# CW340_SAM3X_MAIN.net
KiCad netlist of a schematic drawn in Altium Designer
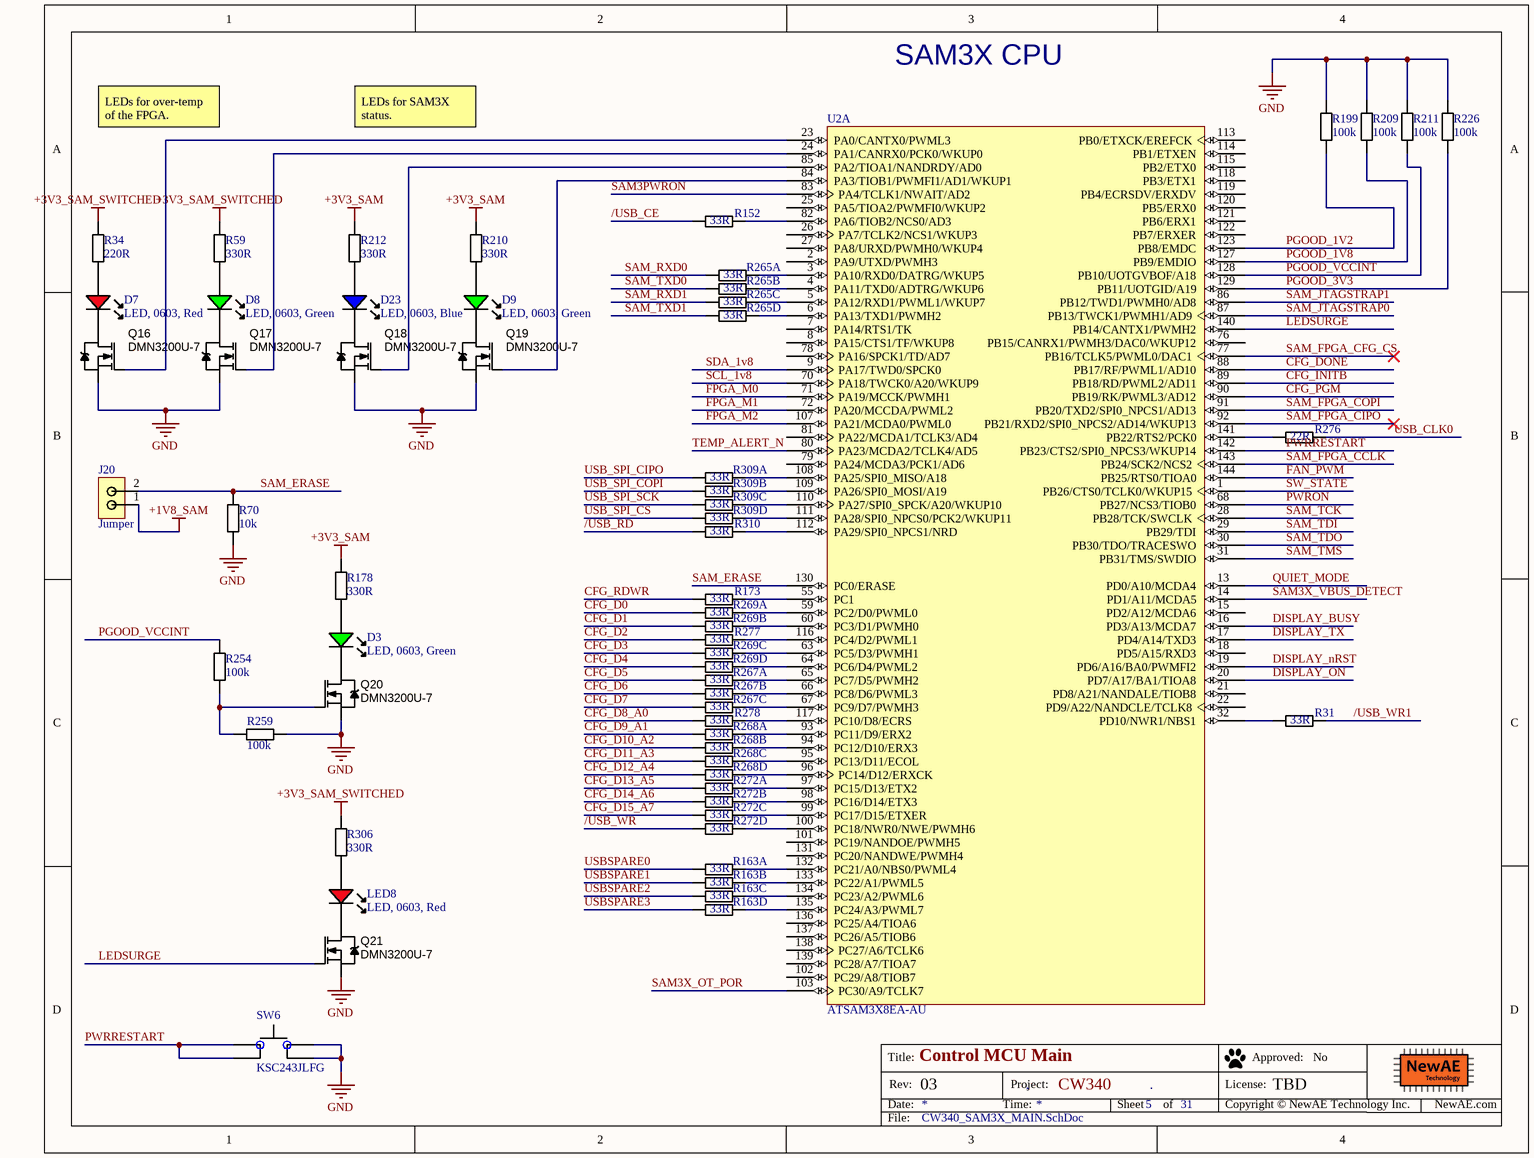
[diagram p0: CW340_SAM3X_MAIN.SchDoc]

(export (version "E")
  (design (tool "Eeschema 10.0.6"))
  (components
    (comp (ref "D3")
      (value "LED, 0603, Green")
      (footprint "LED-0603-GREEN")
      (description "Chip LED, Green")
      (fields (field (name "PART NUMBER") "LEDCHIP_0603_GREEN"))
      (libsource (lib "NewAE_AltiumLib") (part "LED_GREEN"))
    )
    (comp (ref "D7")
      (value "LED, 0603, Red")
      (footprint "LED-0603-RED")
      (description "Chip LED, Red")
      (fields (field (name "PART NUMBER") "LEDCHIP_0603_RED"))
      (libsource (lib "NewAE_AltiumLib") (part "LED_RED"))
    )
    (comp (ref "D8")
      (value "LED, 0603, Green")
      (footprint "LED-0603-GREEN")
      (description "Chip LED, Green")
      (fields (field (name "PART NUMBER") "LEDCHIP_0603_GREEN"))
      (libsource (lib "NewAE_AltiumLib") (part "LED_GREEN"))
    )
    (comp (ref "D9")
      (value "LED, 0603, Green")
      (footprint "LED-0603-GREEN")
      (description "Chip LED, Green")
      (fields (field (name "PART NUMBER") "LEDCHIP_0603_GREEN"))
      (libsource (lib "NewAE_AltiumLib") (part "LED_GREEN"))
    )
    (comp (ref "D23")
      (value "LED, 0603, Blue")
      (footprint "LED-0603-BLUE")
      (description "Chip LED, Blue")
      (fields (field (name "PART NUMBER") "LEDCHIP_0603_BLUE"))
      (libsource (lib "NewAE_AltiumLib") (part "LED_BLUE"))
    )
    (comp (ref "J20")
      (value "Jumper")
      (footprint "2x2.54mm_Header")
      (description "1x2 2.54mm header, male pins")
      (fields (field (name "PART NUMBER") "2_PIN_JUMPER"))
      (libsource (lib "NewAE_AltiumLib") (part "1x2_Pin_Header"))
    )
    (comp (ref "LED8")
      (value "LED, 0603, Red")
      (footprint "LED-0603-RED")
      (description "Chip LED, Red")
      (fields (field (name "PART NUMBER") "LEDCHIP_0603_RED"))
      (libsource (lib "NewAE_AltiumLib") (part "LED_RED"))
    )
    (comp (ref "Q16")
      (value "DMN3200U-7")
      (footprint "SOT95P245X110-3M")
      (description "MOSFET N-CH 30V 2.2A SOT23-3")
      (libsource (lib "NewAE_AltiumLib") (part "MOSFET_N_GSD"))
    )
    (comp (ref "Q17")
      (value "DMN3200U-7")
      (footprint "SOT95P245X110-3M")
      (description "MOSFET N-CH 30V 2.2A SOT23-3")
      (libsource (lib "NewAE_AltiumLib") (part "MOSFET_N_GSD"))
    )
    (comp (ref "Q18")
      (value "DMN3200U-7")
      (footprint "SOT95P245X110-3M")
      (description "MOSFET N-CH 30V 2.2A SOT23-3")
      (libsource (lib "NewAE_AltiumLib") (part "MOSFET_N_GSD"))
    )
    (comp (ref "Q19")
      (value "DMN3200U-7")
      (footprint "SOT95P245X110-3M")
      (description "MOSFET N-CH 30V 2.2A SOT23-3")
      (libsource (lib "NewAE_AltiumLib") (part "MOSFET_N_GSD"))
    )
    (comp (ref "Q20")
      (value "DMN3200U-7")
      (footprint "SOT95P245X110-3M")
      (description "MOSFET N-CH 30V 2.2A SOT23-3")
      (libsource (lib "NewAE_AltiumLib") (part "MOSFET_N_GSD"))
    )
    (comp (ref "Q21")
      (value "DMN3200U-7")
      (footprint "SOT95P245X110-3M")
      (description "MOSFET N-CH 30V 2.2A SOT23-3")
      (libsource (lib "NewAE_AltiumLib") (part "MOSFET_N_GSD"))
    )
    (comp (ref "R31")
      (value "33R")
      (footprint "RESC1005X40N")
      (description "33R res, 0402, 1%, 1/16W")
      (fields (field (name "PART NUMBER") "RCHIP-33R-0402") (field (name "TOLERANCE") "1%"))
      (libsource (lib "NewAE_AltiumLib") (part "RES-EU"))
    )
    (comp (ref "R34")
      (value "220R")
      (footprint "RESC1608X55N")
      (description "220R res, 0603, 1%, 1/10W")
      (fields (field (name "PART NUMBER") "RCHIP-220R-0603") (field (name "TOLERANCE") "1%"))
      (libsource (lib "") (part "RES-EU_1"))
    )
    (comp (ref "R59")
      (value "330R")
      (footprint "RESC1608X55N")
      (description "330R res, 0603, 1%, 1/10W")
      (fields (field (name "PART NUMBER") "RCHIP-330R-0603") (field (name "TOLERANCE") "1%"))
      (libsource (lib "") (part "RES-EU_1"))
    )
    (comp (ref "R70")
      (value "10k")
      (footprint "RESC1005X40N")
      (description "10k res, 0402, 1%, 1/16W")
      (fields (field (name "PART NUMBER") "RCHIP-10K-0402") (field (name "TOLERANCE") "1%"))
      (libsource (lib "") (part "RES-EU_2"))
    )
    (comp (ref "R152")
      (value "33R")
      (footprint "RESC1005X40N")
      (description "33R res, 0402, 1%, 1/16W")
      (fields (field (name "PART NUMBER") "RCHIP-33R-0402") (field (name "TOLERANCE") "1%"))
      (libsource (lib "NewAE_AltiumLib") (part "RES-EU"))
    )
    (comp (ref "R163")
      (value "33R")
      (footprint "741C083")
      (description "33-ohm, 0.5mm res array")
      (fields (field (name "PART NUMBER") "741C083330JP"))
      (libsource (lib "NewAE_AltiumLib") (part "RES-EU-4ARRAY"))
    )
    (comp (ref "R173")
      (value "33R")
      (footprint "RESC1005X40N")
      (description "33R res, 0402, 1%, 1/16W")
      (fields (field (name "PART NUMBER") "RCHIP-33R-0402") (field (name "TOLERANCE") "1%"))
      (libsource (lib "NewAE_AltiumLib") (part "RES-EU"))
    )
    (comp (ref "R178")
      (value "330R")
      (footprint "RESC1608X55N")
      (description "330R res, 0603, 1%, 1/10W")
      (fields (field (name "PART NUMBER") "RCHIP-330R-0603") (field (name "TOLERANCE") "1%"))
      (libsource (lib "") (part "RES-EU_1"))
    )
    (comp (ref "R199")
      (value "100k")
      (footprint "RESC1608X55N")
      (description "100k res, 0603, 1%, 1/10W")
      (fields (field (name "PART NUMBER") "RCHIP-100K-0603") (field (name "TOLERANCE") "1%"))
      (libsource (lib "") (part "RES-EU_2"))
    )
    (comp (ref "R209")
      (value "100k")
      (footprint "RESC1608X55N")
      (description "100k res, 0603, 1%, 1/10W")
      (fields (field (name "PART NUMBER") "RCHIP-100K-0603") (field (name "TOLERANCE") "1%"))
      (libsource (lib "") (part "RES-EU_2"))
    )
    (comp (ref "R210")
      (value "330R")
      (footprint "RESC1608X55N")
      (description "330R res, 0603, 1%, 1/10W")
      (fields (field (name "PART NUMBER") "RCHIP-330R-0603") (field (name "TOLERANCE") "1%"))
      (libsource (lib "") (part "RES-EU_1"))
    )
    (comp (ref "R211")
      (value "100k")
      (footprint "RESC1608X55N")
      (description "100k res, 0603, 1%, 1/10W")
      (fields (field (name "PART NUMBER") "RCHIP-100K-0603") (field (name "TOLERANCE") "1%"))
      (libsource (lib "") (part "RES-EU_2"))
    )
    (comp (ref "R212")
      (value "330R")
      (footprint "RESC1608X55N")
      (description "330R res, 0603, 1%, 1/10W")
      (fields (field (name "PART NUMBER") "RCHIP-330R-0603") (field (name "TOLERANCE") "1%"))
      (libsource (lib "") (part "RES-EU_1"))
    )
    (comp (ref "R226")
      (value "100k")
      (footprint "RESC1608X55N")
      (description "100k res, 0603, 1%, 1/10W")
      (fields (field (name "PART NUMBER") "RCHIP-100K-0603") (field (name "TOLERANCE") "1%"))
      (libsource (lib "") (part "RES-EU_2"))
    )
    (comp (ref "R254")
      (value "100k")
      (footprint "RESC1608X55N")
      (description "100k res, 0603, 1%, 1/10W")
      (fields (field (name "PART NUMBER") "RCHIP-100K-0603") (field (name "TOLERANCE") "1%"))
      (libsource (lib "") (part "RES-EU_2"))
    )
    (comp (ref "R259")
      (value "100k")
      (footprint "RESC1608X55N")
      (description "100k res, 0603, 1%, 1/10W")
      (fields (field (name "PART NUMBER") "RCHIP-100K-0603") (field (name "TOLERANCE") "1%"))
      (libsource (lib "NewAE_AltiumLib") (part "RES-EU"))
    )
    (comp (ref "R265")
      (value "33R")
      (footprint "741C083")
      (description "33-ohm, 0.5mm res array")
      (fields (field (name "PART NUMBER") "741C083330JP"))
      (libsource (lib "NewAE_AltiumLib") (part "RES-EU-4ARRAY"))
    )
    (comp (ref "R267")
      (value "33R")
      (footprint "741C083")
      (description "33-ohm, 0.5mm res array")
      (fields (field (name "PART NUMBER") "741C083330JP"))
      (libsource (lib "NewAE_AltiumLib") (part "RES-EU-4ARRAY"))
    )
    (comp (ref "R268")
      (value "33R")
      (footprint "741C083")
      (description "33-ohm, 0.5mm res array")
      (fields (field (name "PART NUMBER") "741C083330JP"))
      (libsource (lib "NewAE_AltiumLib") (part "RES-EU-4ARRAY"))
    )
    (comp (ref "R269")
      (value "33R")
      (footprint "741C083")
      (description "33-ohm, 0.5mm res array")
      (fields (field (name "PART NUMBER") "741C083330JP"))
      (libsource (lib "NewAE_AltiumLib") (part "RES-EU-4ARRAY"))
    )
    (comp (ref "R272")
      (value "33R")
      (footprint "741C083")
      (description "33-ohm, 0.5mm res array")
      (fields (field (name "PART NUMBER") "741C083330JP"))
      (libsource (lib "NewAE_AltiumLib") (part "RES-EU-4ARRAY"))
    )
    (comp (ref "R276")
      (value "22R")
      (footprint "RESC1005X40N")
      (description "22R res, 0402, 1%, 1/16W")
      (fields (field (name "PART NUMBER") "RCHIP-22R-0402") (field (name "TOLERANCE") "1%"))
      (libsource (lib "NewAE_AltiumLib") (part "RES-EU"))
    )
    (comp (ref "R277")
      (value "33R")
      (footprint "RESC1005X40N")
      (description "33R res, 0402, 1%, 1/16W")
      (fields (field (name "PART NUMBER") "RCHIP-33R-0402") (field (name "TOLERANCE") "1%"))
      (libsource (lib "NewAE_AltiumLib") (part "RES-EU"))
    )
    (comp (ref "R278")
      (value "33R")
      (footprint "RESC1005X40N")
      (description "33R res, 0402, 1%, 1/16W")
      (fields (field (name "PART NUMBER") "RCHIP-33R-0402") (field (name "TOLERANCE") "1%"))
      (libsource (lib "NewAE_AltiumLib") (part "RES-EU"))
    )
    (comp (ref "R306")
      (value "330R")
      (footprint "RESC1608X55N")
      (description "330R res, 0603, 1%, 1/10W")
      (fields (field (name "PART NUMBER") "RCHIP-330R-0603") (field (name "TOLERANCE") "1%"))
      (libsource (lib "") (part "RES-EU_1"))
    )
    (comp (ref "R309")
      (value "33R")
      (footprint "741C083")
      (description "33-ohm, 0.5mm res array")
      (fields (field (name "PART NUMBER") "741C083330JP"))
      (libsource (lib "NewAE_AltiumLib") (part "RES-EU-4ARRAY"))
    )
    (comp (ref "R310")
      (value "33R")
      (footprint "RESC1005X40N")
      (description "33R res, 0402, 1%, 1/16W")
      (fields (field (name "PART NUMBER") "RCHIP-33R-0402") (field (name "TOLERANCE") "1%"))
      (libsource (lib "NewAE_AltiumLib") (part "RES-EU"))
    )
    (comp (ref "SW6")
      (value "KSC243JLFG")
      (footprint "CK_KSC2J")
      (description "SWITCH TACTILE SPST-NO 0.01A 32V")
      (fields (field (name "PART NUMBER") "TACTSW-KSC243J"))
      (libsource (lib "NewAE_AltiumLib") (part "SW_PB_NO_4PIN_TACT"))
    )
    (comp (ref "U2")
      (value "ATSAM3X8EA-AU")
      (footprint "LQFP144_L")
      (fields (field (name "MANUFACTURER") "Atmel"))
      (libsource (lib "Altium Content Vault") (part "ATML-ATSAM3X-LQFP-144"))
    )
  )
  (nets
    (net (code "1") (name "+1V8_SAM") (class "Default")
      (node (ref "J20") (pin "1") (pinfunction "1_1") (pintype "passive"))
    )
    (net (code "2") (name "+3V3_SAM") (class "Default")
      (node (ref "R178") (pin "2") (pinfunction "2_2") (pintype "passive"))
      (node (ref "R210") (pin "2") (pinfunction "2_2") (pintype "passive"))
      (node (ref "R212") (pin "2") (pinfunction "2_2") (pintype "passive"))
    )
    (net (code "3") (name "+3V3_SAM_SWITCHED") (class "Default")
      (node (ref "R306") (pin "2") (pinfunction "2_2") (pintype "passive"))
      (node (ref "R34") (pin "2") (pinfunction "2_2") (pintype "passive"))
      (node (ref "R59") (pin "2") (pinfunction "2_2") (pintype "passive"))
    )
    (net (code "4") (name "/CFG_D0") (class "Default")
      (node (ref "R269") (pin "1A") (pinfunction "1A_1A") (pintype "passive"))
    )
    (net (code "5") (name "/CFG_D1") (class "Default")
      (node (ref "R269") (pin "2A") (pinfunction "2A_2A") (pintype "passive"))
    )
    (net (code "6") (name "/CFG_D2") (class "Default")
      (node (ref "R277") (pin "1") (pinfunction "1_1") (pintype "passive"))
    )
    (net (code "7") (name "/CFG_D3") (class "Default")
      (node (ref "R269") (pin "3A") (pinfunction "3A_3A") (pintype "passive"))
    )
    (net (code "8") (name "/CFG_D4") (class "Default")
      (node (ref "R269") (pin "4A") (pinfunction "4A_4A") (pintype "passive"))
    )
    (net (code "9") (name "/CFG_D5") (class "Default")
      (node (ref "R267") (pin "1A") (pinfunction "1A_1A") (pintype "passive"))
    )
    (net (code "10") (name "/CFG_D6") (class "Default")
      (node (ref "R267") (pin "2A") (pinfunction "2A_2A") (pintype "passive"))
    )
    (net (code "11") (name "/CFG_D7") (class "Default")
      (node (ref "R267") (pin "3A") (pinfunction "3A_3A") (pintype "passive"))
    )
    (net (code "12") (name "/CFG_D8_A0") (class "Default")
      (node (ref "R278") (pin "1") (pinfunction "1_1") (pintype "passive"))
    )
    (net (code "13") (name "/CFG_D9_A1") (class "Default")
      (node (ref "R268") (pin "1A") (pinfunction "1A_1A") (pintype "passive"))
    )
    (net (code "14") (name "/CFG_D10_A2") (class "Default")
      (node (ref "R268") (pin "2A") (pinfunction "2A_2A") (pintype "passive"))
    )
    (net (code "15") (name "/CFG_D11_A3") (class "Default")
      (node (ref "R268") (pin "3A") (pinfunction "3A_3A") (pintype "passive"))
    )
    (net (code "16") (name "/CFG_D12_A4") (class "Default")
      (node (ref "R268") (pin "4A") (pinfunction "4A_4A") (pintype "passive"))
    )
    (net (code "17") (name "/CFG_D13_A5") (class "Default")
      (node (ref "R272") (pin "1A") (pinfunction "1A_1A") (pintype "passive"))
    )
    (net (code "18") (name "/CFG_D14_A6") (class "Default")
      (node (ref "R272") (pin "2A") (pinfunction "2A_2A") (pintype "passive"))
    )
    (net (code "19") (name "/CFG_D15_A7") (class "Default")
      (node (ref "R272") (pin "3A") (pinfunction "3A_3A") (pintype "passive"))
    )
    (net (code "20") (name "/CFG_DONE") (class "Default")
      (node (ref "U2") (pin "88") (pinfunction "PB17/RF/PWML1/AD10_88") (pintype "bidirectional"))
    )
    (net (code "21") (name "/CFG_INITB") (class "Default")
      (node (ref "U2") (pin "89") (pinfunction "PB18/RD/PWML2/AD11_89") (pintype "bidirectional"))
    )
    (net (code "22") (name "/CFG_PGM") (class "Default")
      (node (ref "U2") (pin "90") (pinfunction "PB19/RK/PWML3/AD12_90") (pintype "bidirectional"))
    )
    (net (code "23") (name "/CFG_RDWR") (class "Default")
      (node (ref "R173") (pin "1") (pinfunction "1_1") (pintype "passive"))
    )
    (net (code "24") (name "/DISPLAY_BUSY") (class "Default")
      (node (ref "U2") (pin "16") (pinfunction "PD3/A13/MCDA7_16") (pintype "bidirectional"))
    )
    (net (code "25") (name "/DISPLAY_ON") (class "Default")
      (node (ref "U2") (pin "20") (pinfunction "PD7/A17/BA1/TIOA8_20") (pintype "bidirectional"))
    )
    (net (code "26") (name "/DISPLAY_TX") (class "Default")
      (node (ref "U2") (pin "17") (pinfunction "PD4/A14/TXD3_17") (pintype "bidirectional"))
    )
    (net (code "27") (name "/DISPLAY_nRST") (class "Default")
      (node (ref "U2") (pin "19") (pinfunction "PD6/A16/BA0/PWMFI2_19") (pintype "bidirectional"))
    )
    (net (code "28") (name "/FAN_PWM") (class "Default")
      (node (ref "U2") (pin "144") (pinfunction "PB25/RTS0/TIOA0_144") (pintype "bidirectional"))
    )
    (net (code "29") (name "/FPGA_M0") (class "Default")
      (node (ref "U2") (pin "71") (pinfunction "PA19/MCCK/PWMH1_71") (pintype "bidirectional"))
    )
    (net (code "30") (name "/FPGA_M1") (class "Default")
      (node (ref "U2") (pin "72") (pinfunction "PA20/MCCDA/PWML2_72") (pintype "bidirectional"))
    )
    (net (code "31") (name "/FPGA_M2") (class "Default")
      (node (ref "U2") (pin "107") (pinfunction "PA21/MCDA0/PWML0_107") (pintype "bidirectional"))
    )
    (net (code "32") (name "/LEDSURGE") (class "Default")
      (node (ref "Q21") (pin "1") (pinfunction "G_1") (pintype "passive"))
      (node (ref "U2") (pin "140") (pinfunction "PB14/CANTX1/PWMH2_140") (pintype "bidirectional"))
    )
    (net (code "33") (name "/PGOOD_1V2") (class "Default")
      (node (ref "R199") (pin "2") (pinfunction "2_2") (pintype "passive"))
      (node (ref "U2") (pin "123") (pinfunction "PB8/EMDC_123") (pintype "bidirectional"))
    )
    (net (code "34") (name "/PGOOD_1V8") (class "Default")
      (node (ref "R209") (pin "2") (pinfunction "2_2") (pintype "passive"))
      (node (ref "U2") (pin "127") (pinfunction "PB9/EMDIO_127") (pintype "bidirectional"))
    )
    (net (code "35") (name "/PGOOD_3V3") (class "Default")
      (node (ref "R226") (pin "2") (pinfunction "2_2") (pintype "passive"))
      (node (ref "U2") (pin "129") (pinfunction "PB11/UOTGID/A19_129") (pintype "bidirectional"))
    )
    (net (code "36") (name "/PGOOD_VCCINT") (class "Default")
      (node (ref "R211") (pin "2") (pinfunction "2_2") (pintype "passive"))
      (node (ref "R254") (pin "1") (pinfunction "1_1") (pintype "passive"))
      (node (ref "U2") (pin "128") (pinfunction "PB10/UOTGVBOF/A18_128") (pintype "bidirectional"))
    )
    (net (code "37") (name "/PWRON") (class "Default")
      (node (ref "U2") (pin "68") (pinfunction "PB27/NCS3/TIOB0_68") (pintype "bidirectional"))
    )
    (net (code "38") (name "/PWRRESTART") (class "Default")
      (node (ref "SW6") (pin "1") (pinfunction "IN_1") (pintype "passive"))
      (node (ref "SW6") (pin "4") (pinfunction "IN_4") (pintype "passive"))
      (node (ref "U2") (pin "142") (pinfunction "PB23/CTS2/SPI0_NPCS3/WKUP14_142") (pintype "bidirectional"))
    )
    (net (code "39") (name "/QUIET_MODE") (class "Default")
      (node (ref "U2") (pin "13") (pinfunction "PD0/A10/MCDA4_13") (pintype "bidirectional"))
    )
    (net (code "40") (name "/SAM3PWRON") (class "Default")
      (node (ref "U2") (pin "83") (pinfunction "PA4/TCLK1/NWAIT/AD2_83") (pintype "bidirectional"))
    )
    (net (code "41") (name "/SAM3X_OT_POR") (class "Default")
      (node (ref "U2") (pin "103") (pinfunction "PC30/A9/TCLK7_103") (pintype "bidirectional"))
    )
    (net (code "42") (name "/SAM3X_VBUS_DETECT") (class "Default")
      (node (ref "U2") (pin "14") (pinfunction "PD1/A11/MCDA5_14") (pintype "bidirectional"))
    )
    (net (code "43") (name "/SAM_ERASE") (class "Default")
      (node (ref "J20") (pin "2") (pinfunction "2_2") (pintype "passive"))
      (node (ref "R70") (pin "1") (pinfunction "1_1") (pintype "passive"))
      (node (ref "U2") (pin "130") (pinfunction "PC0/ERASE_130") (pintype "bidirectional"))
    )
    (net (code "44") (name "/SAM_FPGA_CCLK") (class "Default")
      (node (ref "U2") (pin "143") (pinfunction "PB24/SCK2/NCS2_143") (pintype "bidirectional"))
    )
    (net (code "45") (name "/SAM_FPGA_CFG_CS") (class "Default")
      (node (ref "U2") (pin "77") (pinfunction "PB16/TCLK5/PWML0/DAC1_77") (pintype "bidirectional+no_connect"))
    )
    (net (code "46") (name "/SAM_FPGA_CIPO") (class "Default")
      (node (ref "U2") (pin "92") (pinfunction "PB21/RXD2/SPI0_NPCS2/AD14/WKUP13_92") (pintype "bidirectional+no_connect"))
    )
    (net (code "47") (name "/SAM_FPGA_COPI") (class "Default")
      (node (ref "U2") (pin "91") (pinfunction "PB20/TXD2/SPI0_NPCS1/AD13_91") (pintype "bidirectional"))
    )
    (net (code "48") (name "/SAM_JTAGSTRAP0") (class "Default")
      (node (ref "U2") (pin "87") (pinfunction "PB13/TWCK1/PWMH1/AD9_87") (pintype "bidirectional"))
    )
    (net (code "49") (name "/SAM_JTAGSTRAP1") (class "Default")
      (node (ref "U2") (pin "86") (pinfunction "PB12/TWD1/PWMH0/AD8_86") (pintype "bidirectional"))
    )
    (net (code "50") (name "/SAM_RXD0") (class "Default")
      (node (ref "R265") (pin "1A") (pinfunction "1A_1A") (pintype "passive"))
    )
    (net (code "51") (name "/SAM_RXD1") (class "Default")
      (node (ref "R265") (pin "3A") (pinfunction "3A_3A") (pintype "passive"))
    )
    (net (code "52") (name "/SAM_TCK") (class "Default")
      (node (ref "U2") (pin "28") (pinfunction "PB28/TCK/SWCLK_28") (pintype "bidirectional"))
    )
    (net (code "53") (name "/SAM_TDI") (class "Default")
      (node (ref "U2") (pin "29") (pinfunction "PB29/TDI_29") (pintype "bidirectional"))
    )
    (net (code "54") (name "/SAM_TDO") (class "Default")
      (node (ref "U2") (pin "30") (pinfunction "PB30/TDO/TRACESWO_30") (pintype "bidirectional"))
    )
    (net (code "55") (name "/SAM_TMS") (class "Default")
      (node (ref "U2") (pin "31") (pinfunction "PB31/TMS/SWDIO_31") (pintype "bidirectional"))
    )
    (net (code "56") (name "/SAM_TXD0") (class "Default")
      (node (ref "R265") (pin "2A") (pinfunction "2A_2A") (pintype "passive"))
    )
    (net (code "57") (name "/SAM_TXD1") (class "Default")
      (node (ref "R265") (pin "4A") (pinfunction "4A_4A") (pintype "passive"))
    )
    (net (code "58") (name "/SCL_1v8") (class "Default")
      (node (ref "U2") (pin "70") (pinfunction "PA18/TWCK0/A20/WKUP9_70") (pintype "bidirectional"))
    )
    (net (code "59") (name "/SDA_1v8") (class "Default")
      (node (ref "U2") (pin "9") (pinfunction "PA17/TWD0/SPCK0_9") (pintype "bidirectional"))
    )
    (net (code "60") (name "/SW_STATE") (class "Default")
      (node (ref "U2") (pin "1") (pinfunction "PB26/CTS0/TCLK0/WKUP15_1") (pintype "bidirectional"))
    )
    (net (code "61") (name "/TEMP_ALERT_N") (class "Default")
      (node (ref "U2") (pin "80") (pinfunction "PA23/MCDA2/TCLK4/AD5_80") (pintype "bidirectional"))
    )
    (net (code "62") (name "/USBSPARE0") (class "Default")
      (node (ref "R163") (pin "1A") (pinfunction "1A_1A") (pintype "passive"))
    )
    (net (code "63") (name "/USBSPARE1") (class "Default")
      (node (ref "R163") (pin "2A") (pinfunction "2A_2A") (pintype "passive"))
    )
    (net (code "64") (name "/USBSPARE2") (class "Default")
      (node (ref "R163") (pin "3A") (pinfunction "3A_3A") (pintype "passive"))
    )
    (net (code "65") (name "/USBSPARE3") (class "Default")
      (node (ref "R163") (pin "4A") (pinfunction "4A_4A") (pintype "passive"))
    )
    (net (code "66") (name "/USB_CLK0") (class "Default")
      (node (ref "R276") (pin "2") (pinfunction "2_2") (pintype "passive"))
    )
    (net (code "67") (name "/USB_SPI_CIPO") (class "Default")
      (node (ref "R309") (pin "1A") (pinfunction "1A_1A") (pintype "passive"))
    )
    (net (code "68") (name "/USB_SPI_COPI") (class "Default")
      (node (ref "R309") (pin "2A") (pinfunction "2A_2A") (pintype "passive"))
    )
    (net (code "69") (name "/USB_SPI_CS") (class "Default")
      (node (ref "R309") (pin "4A") (pinfunction "4A_4A") (pintype "passive"))
    )
    (net (code "70") (name "/USB_SPI_SCK") (class "Default")
      (node (ref "R309") (pin "3A") (pinfunction "3A_3A") (pintype "passive"))
    )
    (net (code "71") (name "/{slash}USB_CE") (class "Default")
      (node (ref "R152") (pin "1") (pinfunction "1_1") (pintype "passive"))
    )
    (net (code "72") (name "/{slash}USB_RD") (class "Default")
      (node (ref "R310") (pin "1") (pinfunction "1_1") (pintype "passive"))
    )
    (net (code "73") (name "/{slash}USB_WR") (class "Default")
      (node (ref "R272") (pin "4A") (pinfunction "4A_4A") (pintype "passive"))
    )
    (net (code "74") (name "/{slash}USB_WR1") (class "Default")
      (node (ref "R31") (pin "2") (pinfunction "2_2") (pintype "passive"))
    )
    (net (code "75") (name "GND") (class "Default")
      (node (ref "Q16") (pin "2") (pinfunction "S_2") (pintype "passive"))
      (node (ref "Q17") (pin "2") (pinfunction "S_2") (pintype "passive"))
      (node (ref "Q18") (pin "2") (pinfunction "S_2") (pintype "passive"))
      (node (ref "Q19") (pin "2") (pinfunction "S_2") (pintype "passive"))
      (node (ref "Q20") (pin "2") (pinfunction "S_2") (pintype "passive"))
      (node (ref "Q21") (pin "2") (pinfunction "S_2") (pintype "passive"))
      (node (ref "R199") (pin "1") (pinfunction "1_1") (pintype "passive"))
      (node (ref "R209") (pin "1") (pinfunction "1_1") (pintype "passive"))
      (node (ref "R211") (pin "1") (pinfunction "1_1") (pintype "passive"))
      (node (ref "R226") (pin "1") (pinfunction "1_1") (pintype "passive"))
      (node (ref "R259") (pin "2") (pinfunction "2_2") (pintype "passive"))
      (node (ref "R70") (pin "2") (pinfunction "2_2") (pintype "passive"))
      (node (ref "SW6") (pin "2") (pinfunction "IN_2") (pintype "passive"))
      (node (ref "SW6") (pin "3") (pinfunction "IN_3") (pintype "passive"))
    )
    (net (code "76") (name "Net-(D3-PadA)") (class "Default")
      (node (ref "D3") (pin "A") (pinfunction "A_A") (pintype "passive"))
      (node (ref "R178") (pin "1") (pinfunction "1_1") (pintype "passive"))
    )
    (net (code "77") (name "Net-(D7-PadA)") (class "Default")
      (node (ref "D7") (pin "A") (pinfunction "A_A") (pintype "passive"))
      (node (ref "R34") (pin "1") (pinfunction "1_1") (pintype "passive"))
    )
    (net (code "78") (name "Net-(D8-PadA)") (class "Default")
      (node (ref "D8") (pin "A") (pinfunction "A_A") (pintype "passive"))
      (node (ref "R59") (pin "1") (pinfunction "1_1") (pintype "passive"))
    )
    (net (code "79") (name "Net-(D9-PadA)") (class "Default")
      (node (ref "D9") (pin "A") (pinfunction "A_A") (pintype "passive"))
      (node (ref "R210") (pin "1") (pinfunction "1_1") (pintype "passive"))
    )
    (net (code "80") (name "Net-(D23-PadA)") (class "Default")
      (node (ref "D23") (pin "A") (pinfunction "A_A") (pintype "passive"))
      (node (ref "R212") (pin "1") (pinfunction "1_1") (pintype "passive"))
    )
    (net (code "81") (name "Net-(LED8-PadA)") (class "Default")
      (node (ref "LED8") (pin "A") (pinfunction "A_A") (pintype "passive"))
      (node (ref "R306") (pin "1") (pinfunction "1_1") (pintype "passive"))
    )
    (net (code "82") (name "Net-(Q16-D)") (class "Default")
      (node (ref "D7") (pin "K") (pinfunction "K_K") (pintype "passive"))
      (node (ref "Q16") (pin "3") (pinfunction "D_3") (pintype "passive"))
    )
    (net (code "83") (name "Net-(Q16-G)") (class "Default")
      (node (ref "Q16") (pin "1") (pinfunction "G_1") (pintype "passive"))
      (node (ref "U2") (pin "23") (pinfunction "PA0/CANTX0/PWML3_23") (pintype "bidirectional"))
    )
    (net (code "84") (name "Net-(Q17-D)") (class "Default")
      (node (ref "D8") (pin "K") (pinfunction "K_K") (pintype "passive"))
      (node (ref "Q17") (pin "3") (pinfunction "D_3") (pintype "passive"))
    )
    (net (code "85") (name "Net-(Q17-G)") (class "Default")
      (node (ref "Q17") (pin "1") (pinfunction "G_1") (pintype "passive"))
      (node (ref "U2") (pin "24") (pinfunction "PA1/CANRX0/PCK0/WKUP0_24") (pintype "bidirectional"))
    )
    (net (code "86") (name "Net-(Q18-D)") (class "Default")
      (node (ref "D23") (pin "K") (pinfunction "K_K") (pintype "passive"))
      (node (ref "Q18") (pin "3") (pinfunction "D_3") (pintype "passive"))
    )
    (net (code "87") (name "Net-(Q18-G)") (class "Default")
      (node (ref "Q18") (pin "1") (pinfunction "G_1") (pintype "passive"))
      (node (ref "U2") (pin "85") (pinfunction "PA2/TIOA1/NANDRDY/AD0_85") (pintype "bidirectional"))
    )
    (net (code "88") (name "Net-(Q19-D)") (class "Default")
      (node (ref "D9") (pin "K") (pinfunction "K_K") (pintype "passive"))
      (node (ref "Q19") (pin "3") (pinfunction "D_3") (pintype "passive"))
    )
    (net (code "89") (name "Net-(Q19-G)") (class "Default")
      (node (ref "Q19") (pin "1") (pinfunction "G_1") (pintype "passive"))
      (node (ref "U2") (pin "84") (pinfunction "PA3/TIOB1/PWMFI1/AD1/WKUP1_84") (pintype "bidirectional"))
    )
    (net (code "90") (name "Net-(Q20-D)") (class "Default")
      (node (ref "D3") (pin "K") (pinfunction "K_K") (pintype "passive"))
      (node (ref "Q20") (pin "3") (pinfunction "D_3") (pintype "passive"))
    )
    (net (code "91") (name "Net-(Q20-G)") (class "Default")
      (node (ref "Q20") (pin "1") (pinfunction "G_1") (pintype "passive"))
      (node (ref "R254") (pin "2") (pinfunction "2_2") (pintype "passive"))
      (node (ref "R259") (pin "1") (pinfunction "1_1") (pintype "passive"))
    )
    (net (code "92") (name "Net-(Q21-D)") (class "Default")
      (node (ref "LED8") (pin "K") (pinfunction "K_K") (pintype "passive"))
      (node (ref "Q21") (pin "3") (pinfunction "D_3") (pintype "passive"))
    )
    (net (code "93") (name "Net-(U2A-PA6{slash}TIOB2{slash}NCS0{slash}AD3)") (class "Default")
      (node (ref "R152") (pin "2") (pinfunction "2_2") (pintype "passive"))
      (node (ref "U2") (pin "82") (pinfunction "PA6/TIOB2/NCS0/AD3_82") (pintype "bidirectional"))
    )
    (net (code "94") (name "Net-(U2A-PA10{slash}RXD0{slash}DATRG{slash}WKUP5)") (class "Default")
      (node (ref "R265") (pin "1B") (pinfunction "1B_1B") (pintype "passive"))
      (node (ref "U2") (pin "3") (pinfunction "PA10/RXD0/DATRG/WKUP5_3") (pintype "bidirectional"))
    )
    (net (code "95") (name "Net-(U2A-PA11{slash}TXD0{slash}ADTRG{slash}WKUP6)") (class "Default")
      (node (ref "R265") (pin "2B") (pinfunction "2B_2B") (pintype "passive"))
      (node (ref "U2") (pin "4") (pinfunction "PA11/TXD0/ADTRG/WKUP6_4") (pintype "bidirectional"))
    )
    (net (code "96") (name "Net-(U2A-PA12{slash}RXD1{slash}PWML1{slash}WKUP7)") (class "Default")
      (node (ref "R265") (pin "3B") (pinfunction "3B_3B") (pintype "passive"))
      (node (ref "U2") (pin "5") (pinfunction "PA12/RXD1/PWML1/WKUP7_5") (pintype "bidirectional"))
    )
    (net (code "97") (name "Net-(U2A-PA13{slash}TXD1{slash}PWMH2)") (class "Default")
      (node (ref "R265") (pin "4B") (pinfunction "4B_4B") (pintype "passive"))
      (node (ref "U2") (pin "6") (pinfunction "PA13/TXD1/PWMH2_6") (pintype "bidirectional"))
    )
    (net (code "98") (name "Net-(U2A-PA25{slash}SPI0_MISO{slash}A18)") (class "Default")
      (node (ref "R309") (pin "1B") (pinfunction "1B_1B") (pintype "passive"))
      (node (ref "U2") (pin "108") (pinfunction "PA25/SPI0_MISO/A18_108") (pintype "bidirectional"))
    )
    (net (code "99") (name "Net-(U2A-PA26{slash}SPI0_MOSI{slash}A19)") (class "Default")
      (node (ref "R309") (pin "2B") (pinfunction "2B_2B") (pintype "passive"))
      (node (ref "U2") (pin "109") (pinfunction "PA26/SPI0_MOSI/A19_109") (pintype "bidirectional"))
    )
    (net (code "100") (name "Net-(U2A-PA27{slash}SPI0_SPCK{slash}A20{slash}WKUP10)") (class "Default")
      (node (ref "R309") (pin "3B") (pinfunction "3B_3B") (pintype "passive"))
      (node (ref "U2") (pin "110") (pinfunction "PA27/SPI0_SPCK/A20/WKUP10_110") (pintype "bidirectional"))
    )
    (net (code "101") (name "Net-(U2A-PA28{slash}SPI0_NPCS0{slash}PCK2{slash}WKUP11)") (class "Default")
      (node (ref "R309") (pin "4B") (pinfunction "4B_4B") (pintype "passive"))
      (node (ref "U2") (pin "111") (pinfunction "PA28/SPI0_NPCS0/PCK2/WKUP11_111") (pintype "bidirectional"))
    )
    (net (code "102") (name "Net-(U2A-PA29{slash}SPI0_NPCS1{slash}NRD)") (class "Default")
      (node (ref "R310") (pin "2") (pinfunction "2_2") (pintype "passive"))
      (node (ref "U2") (pin "112") (pinfunction "PA29/SPI0_NPCS1/NRD_112") (pintype "bidirectional"))
    )
    (net (code "103") (name "Net-(U2A-PB22{slash}RTS2{slash}PCK0)") (class "Default")
      (node (ref "R276") (pin "1") (pinfunction "1_1") (pintype "passive"))
      (node (ref "U2") (pin "141") (pinfunction "PB22/RTS2/PCK0_141") (pintype "bidirectional"))
    )
    (net (code "104") (name "Net-(U2A-PC1)") (class "Default")
      (node (ref "R173") (pin "2") (pinfunction "2_2") (pintype "passive"))
      (node (ref "U2") (pin "55") (pinfunction "PC1_55") (pintype "bidirectional"))
    )
    (net (code "105") (name "Net-(U2A-PC2{slash}D0{slash}PWML0)") (class "Default")
      (node (ref "R269") (pin "1B") (pinfunction "1B_1B") (pintype "passive"))
      (node (ref "U2") (pin "59") (pinfunction "PC2/D0/PWML0_59") (pintype "bidirectional"))
    )
    (net (code "106") (name "Net-(U2A-PC3{slash}D1{slash}PWMH0)") (class "Default")
      (node (ref "R269") (pin "2B") (pinfunction "2B_2B") (pintype "passive"))
      (node (ref "U2") (pin "60") (pinfunction "PC3/D1/PWMH0_60") (pintype "bidirectional"))
    )
    (net (code "107") (name "Net-(U2A-PC4{slash}D2{slash}PWML1)") (class "Default")
      (node (ref "R277") (pin "2") (pinfunction "2_2") (pintype "passive"))
      (node (ref "U2") (pin "116") (pinfunction "PC4/D2/PWML1_116") (pintype "bidirectional"))
    )
    (net (code "108") (name "Net-(U2A-PC5{slash}D3{slash}PWMH1)") (class "Default")
      (node (ref "R269") (pin "3B") (pinfunction "3B_3B") (pintype "passive"))
      (node (ref "U2") (pin "63") (pinfunction "PC5/D3/PWMH1_63") (pintype "bidirectional"))
    )
    (net (code "109") (name "Net-(U2A-PC6{slash}D4{slash}PWML2)") (class "Default")
      (node (ref "R269") (pin "4B") (pinfunction "4B_4B") (pintype "passive"))
      (node (ref "U2") (pin "64") (pinfunction "PC6/D4/PWML2_64") (pintype "bidirectional"))
    )
    (net (code "110") (name "Net-(U2A-PC7{slash}D5{slash}PWMH2)") (class "Default")
      (node (ref "R267") (pin "1B") (pinfunction "1B_1B") (pintype "passive"))
      (node (ref "U2") (pin "65") (pinfunction "PC7/D5/PWMH2_65") (pintype "bidirectional"))
    )
    (net (code "111") (name "Net-(U2A-PC8{slash}D6{slash}PWML3)") (class "Default")
      (node (ref "R267") (pin "2B") (pinfunction "2B_2B") (pintype "passive"))
      (node (ref "U2") (pin "66") (pinfunction "PC8/D6/PWML3_66") (pintype "bidirectional"))
    )
    (net (code "112") (name "Net-(U2A-PC9{slash}D7{slash}PWMH3)") (class "Default")
      (node (ref "R267") (pin "3B") (pinfunction "3B_3B") (pintype "passive"))
      (node (ref "U2") (pin "67") (pinfunction "PC9/D7/PWMH3_67") (pintype "bidirectional"))
    )
    (net (code "113") (name "Net-(U2A-PC10{slash}D8{slash}ECRS)") (class "Default")
      (node (ref "R278") (pin "2") (pinfunction "2_2") (pintype "passive"))
      (node (ref "U2") (pin "117") (pinfunction "PC10/D8/ECRS_117") (pintype "bidirectional"))
    )
    (net (code "114") (name "Net-(U2A-PC11{slash}D9{slash}ERX2)") (class "Default")
      (node (ref "R268") (pin "1B") (pinfunction "1B_1B") (pintype "passive"))
      (node (ref "U2") (pin "93") (pinfunction "PC11/D9/ERX2_93") (pintype "bidirectional"))
    )
    (net (code "115") (name "Net-(U2A-PC12{slash}D10{slash}ERX3)") (class "Default")
      (node (ref "R268") (pin "2B") (pinfunction "2B_2B") (pintype "passive"))
      (node (ref "U2") (pin "94") (pinfunction "PC12/D10/ERX3_94") (pintype "bidirectional"))
    )
    (net (code "116") (name "Net-(U2A-PC13{slash}D11{slash}ECOL)") (class "Default")
      (node (ref "R268") (pin "3B") (pinfunction "3B_3B") (pintype "passive"))
      (node (ref "U2") (pin "95") (pinfunction "PC13/D11/ECOL_95") (pintype "bidirectional"))
    )
    (net (code "117") (name "Net-(U2A-PC14{slash}D12{slash}ERXCK)") (class "Default")
      (node (ref "R268") (pin "4B") (pinfunction "4B_4B") (pintype "passive"))
      (node (ref "U2") (pin "96") (pinfunction "PC14/D12/ERXCK_96") (pintype "bidirectional"))
    )
    (net (code "118") (name "Net-(U2A-PC15{slash}D13{slash}ETX2)") (class "Default")
      (node (ref "R272") (pin "1B") (pinfunction "1B_1B") (pintype "passive"))
      (node (ref "U2") (pin "97") (pinfunction "PC15/D13/ETX2_97") (pintype "bidirectional"))
    )
    (net (code "119") (name "Net-(U2A-PC16{slash}D14{slash}ETX3)") (class "Default")
      (node (ref "R272") (pin "2B") (pinfunction "2B_2B") (pintype "passive"))
      (node (ref "U2") (pin "98") (pinfunction "PC16/D14/ETX3_98") (pintype "bidirectional"))
    )
    (net (code "120") (name "Net-(U2A-PC17{slash}D15{slash}ETXER)") (class "Default")
      (node (ref "R272") (pin "3B") (pinfunction "3B_3B") (pintype "passive"))
      (node (ref "U2") (pin "99") (pinfunction "PC17/D15/ETXER_99") (pintype "bidirectional"))
    )
    (net (code "121") (name "Net-(U2A-PC18{slash}NWR0{slash}NWE{slash}PWMH6)") (class "Default")
      (node (ref "R272") (pin "4B") (pinfunction "4B_4B") (pintype "passive"))
      (node (ref "U2") (pin "100") (pinfunction "PC18/NWR0/NWE/PWMH6_100") (pintype "bidirectional"))
    )
    (net (code "122") (name "Net-(U2A-PC21{slash}A0{slash}NBS0{slash}PWML4)") (class "Default")
      (node (ref "R163") (pin "1B") (pinfunction "1B_1B") (pintype "passive"))
      (node (ref "U2") (pin "132") (pinfunction "PC21/A0/NBS0/PWML4_132") (pintype "bidirectional"))
    )
    (net (code "123") (name "Net-(U2A-PC22{slash}A1{slash}PWML5)") (class "Default")
      (node (ref "R163") (pin "2B") (pinfunction "2B_2B") (pintype "passive"))
      (node (ref "U2") (pin "133") (pinfunction "PC22/A1/PWML5_133") (pintype "bidirectional"))
    )
    (net (code "124") (name "Net-(U2A-PC23{slash}A2{slash}PWML6)") (class "Default")
      (node (ref "R163") (pin "3B") (pinfunction "3B_3B") (pintype "passive"))
      (node (ref "U2") (pin "134") (pinfunction "PC23/A2/PWML6_134") (pintype "bidirectional"))
    )
    (net (code "125") (name "Net-(U2A-PC24{slash}A3{slash}PWML7)") (class "Default")
      (node (ref "R163") (pin "4B") (pinfunction "4B_4B") (pintype "passive"))
      (node (ref "U2") (pin "135") (pinfunction "PC24/A3/PWML7_135") (pintype "bidirectional"))
    )
    (net (code "126") (name "Net-(U2A-PD10{slash}NWR1{slash}NBS1)") (class "Default")
      (node (ref "R31") (pin "1") (pinfunction "1_1") (pintype "passive"))
      (node (ref "U2") (pin "32") (pinfunction "PD10/NWR1/NBS1_32") (pintype "bidirectional"))
    )
    (net (code "127") (name "unconnected-(U2A-PA5{slash}TIOA2{slash}PWMFI0{slash}WKUP2-Pad25)") (class "Default")
      (node (ref "U2") (pin "25") (pinfunction "PA5/TIOA2/PWMFI0/WKUP2_25") (pintype "bidirectional"))
    )
    (net (code "128") (name "unconnected-(U2A-PA7{slash}TCLK2{slash}NCS1{slash}WKUP3-Pad26)") (class "Default")
      (node (ref "U2") (pin "26") (pinfunction "PA7/TCLK2/NCS1/WKUP3_26") (pintype "bidirectional"))
    )
    (net (code "129") (name "unconnected-(U2A-PA8{slash}URXD{slash}PWMH0{slash}WKUP4-Pad27)") (class "Default")
      (node (ref "U2") (pin "27") (pinfunction "PA8/URXD/PWMH0/WKUP4_27") (pintype "bidirectional"))
    )
    (net (code "130") (name "unconnected-(U2A-PA9{slash}UTXD{slash}PWMH3-Pad2)") (class "Default")
      (node (ref "U2") (pin "2") (pinfunction "PA9/UTXD/PWMH3_2") (pintype "bidirectional"))
    )
    (net (code "131") (name "unconnected-(U2A-PA14{slash}RTS1{slash}TK-Pad7)") (class "Default")
      (node (ref "U2") (pin "7") (pinfunction "PA14/RTS1/TK_7") (pintype "bidirectional"))
    )
    (net (code "132") (name "unconnected-(U2A-PA15{slash}CTS1{slash}TF{slash}WKUP8-Pad8)") (class "Default")
      (node (ref "U2") (pin "8") (pinfunction "PA15/CTS1/TF/WKUP8_8") (pintype "bidirectional"))
    )
    (net (code "133") (name "unconnected-(U2A-PA16{slash}SPCK1{slash}TD{slash}AD7-Pad78)") (class "Default")
      (node (ref "U2") (pin "78") (pinfunction "PA16/SPCK1/TD/AD7_78") (pintype "bidirectional"))
    )
    (net (code "134") (name "unconnected-(U2A-PA22{slash}MCDA1{slash}TCLK3{slash}AD4-Pad81)") (class "Default")
      (node (ref "U2") (pin "81") (pinfunction "PA22/MCDA1/TCLK3/AD4_81") (pintype "bidirectional"))
    )
    (net (code "135") (name "unconnected-(U2A-PA24{slash}MCDA3{slash}PCK1{slash}AD6-Pad79)") (class "Default")
      (node (ref "U2") (pin "79") (pinfunction "PA24/MCDA3/PCK1/AD6_79") (pintype "bidirectional"))
    )
    (net (code "136") (name "unconnected-(U2A-PB0{slash}ETXCK{slash}EREFCK-Pad113)") (class "Default")
      (node (ref "U2") (pin "113") (pinfunction "PB0/ETXCK/EREFCK_113") (pintype "bidirectional"))
    )
    (net (code "137") (name "unconnected-(U2A-PB1{slash}ETXEN-Pad114)") (class "Default")
      (node (ref "U2") (pin "114") (pinfunction "PB1/ETXEN_114") (pintype "bidirectional"))
    )
    (net (code "138") (name "unconnected-(U2A-PB2{slash}ETX0-Pad115)") (class "Default")
      (node (ref "U2") (pin "115") (pinfunction "PB2/ETX0_115") (pintype "bidirectional"))
    )
    (net (code "139") (name "unconnected-(U2A-PB3{slash}ETX1-Pad118)") (class "Default")
      (node (ref "U2") (pin "118") (pinfunction "PB3/ETX1_118") (pintype "bidirectional"))
    )
    (net (code "140") (name "unconnected-(U2A-PB4{slash}ECRSDV{slash}ERXDV-Pad119)") (class "Default")
      (node (ref "U2") (pin "119") (pinfunction "PB4/ECRSDV/ERXDV_119") (pintype "bidirectional"))
    )
    (net (code "141") (name "unconnected-(U2A-PB5{slash}ERX0-Pad120)") (class "Default")
      (node (ref "U2") (pin "120") (pinfunction "PB5/ERX0_120") (pintype "bidirectional"))
    )
    (net (code "142") (name "unconnected-(U2A-PB6{slash}ERX1-Pad121)") (class "Default")
      (node (ref "U2") (pin "121") (pinfunction "PB6/ERX1_121") (pintype "bidirectional"))
    )
    (net (code "143") (name "unconnected-(U2A-PB7{slash}ERXER-Pad122)") (class "Default")
      (node (ref "U2") (pin "122") (pinfunction "PB7/ERXER_122") (pintype "bidirectional"))
    )
    (net (code "144") (name "unconnected-(U2A-PB15{slash}CANRX1{slash}PWMH3{slash}DAC0{slash}WKUP12-Pad76)") (class "Default")
      (node (ref "U2") (pin "76") (pinfunction "PB15/CANRX1/PWMH3/DAC0/WKUP12_76") (pintype "bidirectional"))
    )
    (net (code "145") (name "unconnected-(U2A-PC19{slash}NANDOE{slash}PWMH5-Pad101)") (class "Default")
      (node (ref "U2") (pin "101") (pinfunction "PC19/NANDOE/PWMH5_101") (pintype "bidirectional"))
    )
    (net (code "146") (name "unconnected-(U2A-PC20{slash}NANDWE{slash}PWMH4-Pad131)") (class "Default")
      (node (ref "U2") (pin "131") (pinfunction "PC20/NANDWE/PWMH4_131") (pintype "bidirectional"))
    )
    (net (code "147") (name "unconnected-(U2A-PC25{slash}A4{slash}TIOA6-Pad136)") (class "Default")
      (node (ref "U2") (pin "136") (pinfunction "PC25/A4/TIOA6_136") (pintype "bidirectional"))
    )
    (net (code "148") (name "unconnected-(U2A-PC26{slash}A5{slash}TIOB6-Pad137)") (class "Default")
      (node (ref "U2") (pin "137") (pinfunction "PC26/A5/TIOB6_137") (pintype "bidirectional"))
    )
    (net (code "149") (name "unconnected-(U2A-PC27{slash}A6{slash}TCLK6-Pad138)") (class "Default")
      (node (ref "U2") (pin "138") (pinfunction "PC27/A6/TCLK6_138") (pintype "bidirectional"))
    )
    (net (code "150") (name "unconnected-(U2A-PC28{slash}A7{slash}TIOA7-Pad139)") (class "Default")
      (node (ref "U2") (pin "139") (pinfunction "PC28/A7/TIOA7_139") (pintype "bidirectional"))
    )
    (net (code "151") (name "unconnected-(U2A-PC29{slash}A8{slash}TIOB7-Pad102)") (class "Default")
      (node (ref "U2") (pin "102") (pinfunction "PC29/A8/TIOB7_102") (pintype "bidirectional"))
    )
    (net (code "152") (name "unconnected-(U2A-PD2{slash}A12{slash}MCDA6-Pad15)") (class "Default")
      (node (ref "U2") (pin "15") (pinfunction "PD2/A12/MCDA6_15") (pintype "bidirectional"))
    )
    (net (code "153") (name "unconnected-(U2A-PD5{slash}A15{slash}RXD3-Pad18)") (class "Default")
      (node (ref "U2") (pin "18") (pinfunction "PD5/A15/RXD3_18") (pintype "bidirectional"))
    )
    (net (code "154") (name "unconnected-(U2A-PD8{slash}A21{slash}NANDALE{slash}TIOB8-Pad21)") (class "Default")
      (node (ref "U2") (pin "21") (pinfunction "PD8/A21/NANDALE/TIOB8_21") (pintype "bidirectional"))
    )
    (net (code "155") (name "unconnected-(U2A-PD9{slash}A22{slash}NANDCLE{slash}TCLK8-Pad22)") (class "Default")
      (node (ref "U2") (pin "22") (pinfunction "PD9/A22/NANDCLE/TCLK8_22") (pintype "bidirectional"))
    )
  )
)
